# MCU.net
KiCad netlist of a schematic drawn in Altium Designer
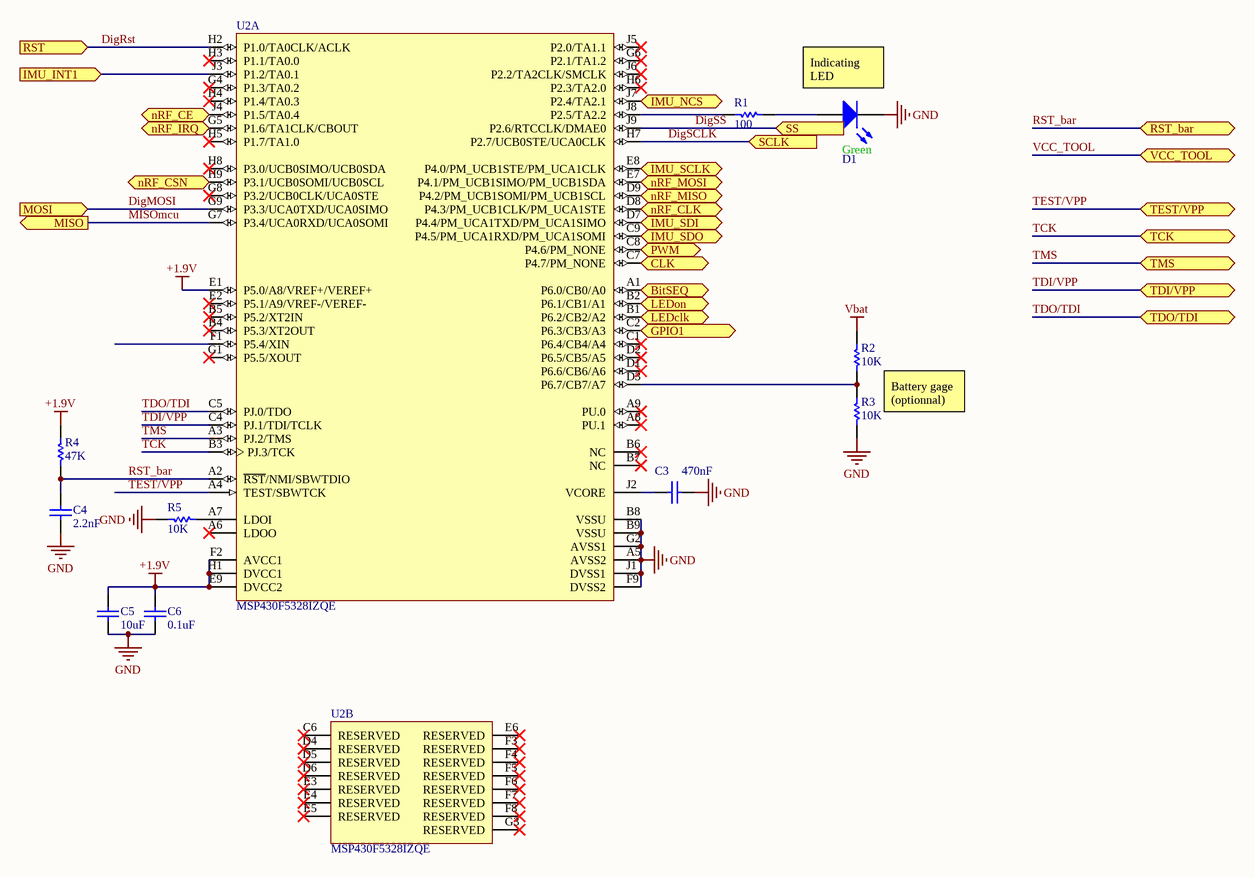
[diagram p0: MCU.SchDoc]

(export (version "E")
  (design (tool "Eeschema 10.0.6"))
  (components
    (comp (ref "C3")
      (value "470nF")
      (footprint "0201_Custom")
      (description "Capacitor (Semiconductor SIM Model)")
      (fields (field (name "PUBLISHER") "Altium Limited"))
      (libsource (lib "Miscellaneous Devices") (part "Cap Semi"))
    )
    (comp (ref "C4")
      (value "2.2nF")
      (footprint "0201_Custom")
      (description "Capacitor (Semiconductor SIM Model)")
      (fields (field (name "PUBLISHER") "Altium Limited"))
      (libsource (lib "Miscellaneous Devices") (part "Cap Semi"))
    )
    (comp (ref "C5")
      (value "10uF")
      (footprint "0402")
      (description "Capacitor (Semiconductor SIM Model)")
      (fields (field (name "PUBLISHER") "Altium Limited"))
      (libsource (lib "Miscellaneous Devices") (part "Cap Semi"))
    )
    (comp (ref "C6")
      (value "0.1uF")
      (footprint "0201_Custom")
      (description "Capacitor (Semiconductor SIM Model)")
      (fields (field (name "PUBLISHER") "Altium Limited"))
      (libsource (lib "Miscellaneous Devices") (part "Cap Semi"))
    )
    (comp (ref "D1")
      (value "~")
      (footprint "0402")
      (description "Typical BLUE SiC LED")
      (fields (field (name "COLOR") "Green") (field (name "PUBLISHER") "Altium Limited"))
      (libsource (lib "Miscellaneous Devices") (part "LED3"))
    )
    (comp (ref "R1")
      (value "100")
      (footprint "0201_Custom")
      (description "Semiconductor Resistor")
      (fields (field (name "PUBLISHER") "Altium Limited"))
      (libsource (lib "Miscellaneous Devices") (part "Res Semi"))
    )
    (comp (ref "R2")
      (value "10K")
      (footprint "0201_Custom")
      (description "Semiconductor Resistor")
      (fields (field (name "PUBLISHER") "Altium Limited"))
      (libsource (lib "Miscellaneous Devices") (part "Res Semi"))
    )
    (comp (ref "R3")
      (value "10K")
      (footprint "0201_Custom")
      (description "Semiconductor Resistor")
      (fields (field (name "PUBLISHER") "Altium Limited"))
      (libsource (lib "Miscellaneous Devices") (part "Res Semi"))
    )
    (comp (ref "R4")
      (value "47K")
      (footprint "0201_Custom")
      (description "Semiconductor Resistor")
      (fields (field (name "PUBLISHER") "Altium Limited"))
      (libsource (lib "Miscellaneous Devices") (part "Res Semi"))
    )
    (comp (ref "R5")
      (value "10K")
      (footprint "0201_Custom")
      (description "Semiconductor Resistor")
      (fields (field (name "PUBLISHER") "Altium Limited"))
      (libsource (lib "Miscellaneous Devices") (part "Res Semi"))
    )
    (comp (ref "U2")
      (value "MSP430F5328IZQE")
      (footprint "TI-ZQE80")
      (fields (field (name "MANUFACTURER") "Texas Instruments"))
      (libsource (lib "TI Microcontroller MSP430 16-bit Ultra-Low Power") (part "MSP430F5328IZQE"))
    )
  )
  (nets
    (net (code "1") (name "+1.9V") (class "Default")
      (node (ref "C5") (pin "2") (pinfunction "2_2") (pintype "passive"))
      (node (ref "C6") (pin "2") (pinfunction "2_2") (pintype "passive"))
      (node (ref "R4") (pin "1") (pinfunction "1_1") (pintype "passive"))
      (node (ref "U2") (pin "E1") (pinfunction "P5.0/A8/VREF+/VEREF+_E1") (pintype "bidirectional"))
      (node (ref "U2") (pin "E9") (pinfunction "DVCC2_E9") (pintype "power_in"))
      (node (ref "U2") (pin "F2") (pinfunction "AVCC1_F2") (pintype "power_in"))
      (node (ref "U2") (pin "H1") (pinfunction "DVCC1_H1") (pintype "power_in"))
    )
    (net (code "2") (name "/BitSEQ") (class "Default")
      (node (ref "U2") (pin "A1") (pinfunction "P6.0/CB0/A0_A1") (pintype "bidirectional"))
    )
    (net (code "3") (name "/CLK") (class "Default")
      (node (ref "U2") (pin "C7") (pinfunction "P4.7/PM_NONE_C7") (pintype "bidirectional"))
    )
    (net (code "4") (name "/DigMOSI") (class "Default")
      (node (ref "U2") (pin "G9") (pinfunction "P3.3/UCA0TXD/UCA0SIMO_G9") (pintype "bidirectional"))
    )
    (net (code "5") (name "/DigRst") (class "Default")
      (node (ref "U2") (pin "H2") (pinfunction "P1.0/TA0CLK/ACLK_H2") (pintype "bidirectional"))
    )
    (net (code "6") (name "/DigSCLK") (class "Default")
      (node (ref "U2") (pin "H7") (pinfunction "P2.7/UCB0STE/UCA0CLK_H7") (pintype "bidirectional"))
    )
    (net (code "7") (name "/DigSS") (class "Default")
      (node (ref "U2") (pin "J9") (pinfunction "P2.6/RTCCLK/DMAE0_J9") (pintype "bidirectional"))
    )
    (net (code "8") (name "/GPIO1") (class "Default")
      (node (ref "U2") (pin "C2") (pinfunction "P6.3/CB3/A3_C2") (pintype "bidirectional"))
    )
    (net (code "9") (name "/IMU_INT1") (class "Default")
      (node (ref "U2") (pin "J3") (pinfunction "P1.2/TA0.1_J3") (pintype "bidirectional"))
    )
    (net (code "10") (name "/IMU_NCS") (class "Default")
      (node (ref "U2") (pin "J7") (pinfunction "P2.4/TA2.1_J7") (pintype "bidirectional"))
    )
    (net (code "11") (name "/IMU_SCLK") (class "Default")
      (node (ref "U2") (pin "E8") (pinfunction "P4.0/PM_UCB1STE/PM_UCA1CLK_E8") (pintype "bidirectional"))
    )
    (net (code "12") (name "/IMU_SDI") (class "Default")
      (node (ref "U2") (pin "D7") (pinfunction "P4.4/PM_UCA1TXD/PM_UCA1SIMO_D7") (pintype "bidirectional"))
    )
    (net (code "13") (name "/IMU_SDO") (class "Default")
      (node (ref "U2") (pin "C9") (pinfunction "P4.5/PM_UCA1RXD/PM_UCA1SOMI_C9") (pintype "bidirectional"))
    )
    (net (code "14") (name "/LEDclk") (class "Default")
      (node (ref "U2") (pin "B1") (pinfunction "P6.2/CB2/A2_B1") (pintype "bidirectional"))
    )
    (net (code "15") (name "/LEDon") (class "Default")
      (node (ref "U2") (pin "B2") (pinfunction "P6.1/CB1/A1_B2") (pintype "bidirectional"))
    )
    (net (code "16") (name "/MISOmcu") (class "Default")
      (node (ref "U2") (pin "G7") (pinfunction "P3.4/UCA0RXD/UCA0SOMI_G7") (pintype "bidirectional"))
    )
    (net (code "17") (name "/PWM") (class "Default")
      (node (ref "U2") (pin "C8") (pinfunction "P4.6/PM_NONE_C8") (pintype "bidirectional"))
    )
    (net (code "18") (name "/RST_bar") (class "Default")
      (node (ref "C4") (pin "1") (pinfunction "1_1") (pintype "passive"))
      (node (ref "R4") (pin "2") (pinfunction "2_2") (pintype "passive"))
      (node (ref "U2") (pin "A2") (pinfunction "~{RST}/NMI/SBWTDIO_A2") (pintype "bidirectional"))
    )
    (net (code "19") (name "/TCK") (class "Default")
      (node (ref "U2") (pin "B3") (pinfunction "PJ.3/TCK_B3") (pintype "bidirectional"))
    )
    (net (code "20") (name "/TDI{slash}VPP") (class "Default")
      (node (ref "U2") (pin "C4") (pinfunction "PJ.1/TDI/TCLK_C4") (pintype "bidirectional"))
    )
    (net (code "21") (name "/TDO{slash}TDI") (class "Default")
      (node (ref "U2") (pin "C5") (pinfunction "PJ.0/TDO_C5") (pintype "bidirectional"))
    )
    (net (code "22") (name "/TEST{slash}VPP") (class "Default")
      (node (ref "U2") (pin "A4") (pinfunction "TEST/SBWTCK_A4") (pintype "input"))
    )
    (net (code "23") (name "/TMS") (class "Default")
      (node (ref "U2") (pin "A3") (pinfunction "PJ.2/TMS_A3") (pintype "bidirectional"))
    )
    (net (code "25") (name "/nRF_CE") (class "Default")
      (node (ref "U2") (pin "J4") (pinfunction "P1.5/TA0.4_J4") (pintype "bidirectional"))
    )
    (net (code "26") (name "/nRF_CLK") (class "Default")
      (node (ref "U2") (pin "D8") (pinfunction "P4.3/PM_UCB1CLK/PM_UCA1STE_D8") (pintype "bidirectional"))
    )
    (net (code "27") (name "/nRF_CSN") (class "Default")
      (node (ref "U2") (pin "H9") (pinfunction "P3.1/UCB0SOMI/UCB0SCL_H9") (pintype "bidirectional"))
    )
    (net (code "28") (name "/nRF_IRQ") (class "Default")
      (node (ref "U2") (pin "G5") (pinfunction "P1.6/TA1CLK/CBOUT_G5") (pintype "bidirectional"))
    )
    (net (code "29") (name "/nRF_MISO") (class "Default")
      (node (ref "U2") (pin "D9") (pinfunction "P4.2/PM_UCB1SOMI/PM_UCB1SCL_D9") (pintype "bidirectional"))
    )
    (net (code "30") (name "/nRF_MOSI") (class "Default")
      (node (ref "U2") (pin "E7") (pinfunction "P4.1/PM_UCB1SIMO/PM_UCB1SDA_E7") (pintype "bidirectional"))
    )
    (net (code "31") (name "GND") (class "Default")
      (node (ref "C3") (pin "1") (pinfunction "1_1") (pintype "passive"))
      (node (ref "C4") (pin "2") (pinfunction "2_2") (pintype "passive"))
      (node (ref "C5") (pin "1") (pinfunction "1_1") (pintype "passive"))
      (node (ref "C6") (pin "1") (pinfunction "1_1") (pintype "passive"))
      (node (ref "D1") (pin "2") (pinfunction "K_2") (pintype "passive"))
      (node (ref "R3") (pin "2") (pinfunction "2_2") (pintype "passive"))
      (node (ref "R5") (pin "2") (pinfunction "2_2") (pintype "passive"))
      (node (ref "U2") (pin "A5") (pinfunction "AVSS2_A5") (pintype "power_in"))
      (node (ref "U2") (pin "B8") (pinfunction "VSSU_B8") (pintype "power_in"))
      (node (ref "U2") (pin "B9") (pinfunction "VSSU_B9") (pintype "power_in"))
      (node (ref "U2") (pin "F9") (pinfunction "DVSS2_F9") (pintype "power_in"))
      (node (ref "U2") (pin "G2") (pinfunction "AVSS1_G2") (pintype "power_in"))
      (node (ref "U2") (pin "J1") (pinfunction "DVSS1_J1") (pintype "power_in"))
    )
    (net (code "32") (name "Net-(D1-A)") (class "Default")
      (node (ref "D1") (pin "1") (pinfunction "A_1") (pintype "passive"))
      (node (ref "R1") (pin "1") (pinfunction "1_1") (pintype "passive"))
    )
    (net (code "33") (name "Net-(U2A-LDOI)") (class "Default")
      (node (ref "R5") (pin "1") (pinfunction "1_1") (pintype "passive"))
      (node (ref "U2") (pin "A7") (pinfunction "LDOI_A7") (pintype "power_in"))
    )
    (net (code "34") (name "Net-(U2A-P2.5{slash}TA2.2)") (class "Default")
      (node (ref "R1") (pin "2") (pinfunction "2_2") (pintype "passive"))
      (node (ref "U2") (pin "J8") (pinfunction "P2.5/TA2.2_J8") (pintype "bidirectional"))
    )
    (net (code "35") (name "Net-(U2A-P6.7{slash}CB7{slash}A7)") (class "Default")
      (node (ref "R2") (pin "2") (pinfunction "2_2") (pintype "passive"))
      (node (ref "R3") (pin "1") (pinfunction "1_1") (pintype "passive"))
      (node (ref "U2") (pin "D3") (pinfunction "P6.7/CB7/A7_D3") (pintype "bidirectional"))
    )
    (net (code "36") (name "Net-(U2A-VCORE)") (class "Default")
      (node (ref "C3") (pin "2") (pinfunction "2_2") (pintype "passive"))
      (node (ref "U2") (pin "J2") (pinfunction "VCORE_J2") (pintype "passive"))
    )
    (net (code "37") (name "Vbat") (class "Default")
      (node (ref "R2") (pin "1") (pinfunction "1_1") (pintype "passive"))
    )
    (net (code "38") (name "unconnected-(U2A-LDOO-PadA6)") (class "Default")
      (node (ref "U2") (pin "A6") (pinfunction "LDOO_A6") (pintype "power_in+no_connect"))
    )
    (net (code "39") (name "unconnected-(U2A-NC-PadB6)") (class "Default")
      (node (ref "U2") (pin "B6") (pinfunction "NC_B6") (pintype "passive+no_connect"))
    )
    (net (code "40") (name "unconnected-(U2A-NC-PadB7)") (class "Default")
      (node (ref "U2") (pin "B7") (pinfunction "NC_B7") (pintype "passive+no_connect"))
    )
    (net (code "41") (name "unconnected-(U2A-P1.1{slash}TA0.0-PadH3)") (class "Default")
      (node (ref "U2") (pin "H3") (pinfunction "P1.1/TA0.0_H3") (pintype "bidirectional+no_connect"))
    )
    (net (code "42") (name "unconnected-(U2A-P1.3{slash}TA0.2-PadG4)") (class "Default")
      (node (ref "U2") (pin "G4") (pinfunction "P1.3/TA0.2_G4") (pintype "bidirectional+no_connect"))
    )
    (net (code "43") (name "unconnected-(U2A-P1.4{slash}TA0.3-PadH4)") (class "Default")
      (node (ref "U2") (pin "H4") (pinfunction "P1.4/TA0.3_H4") (pintype "bidirectional+no_connect"))
    )
    (net (code "44") (name "unconnected-(U2A-P1.7{slash}TA1.0-PadH5)") (class "Default")
      (node (ref "U2") (pin "H5") (pinfunction "P1.7/TA1.0_H5") (pintype "bidirectional+no_connect"))
    )
    (net (code "45") (name "unconnected-(U2A-P2.0{slash}TA1.1-PadJ5)") (class "Default")
      (node (ref "U2") (pin "J5") (pinfunction "P2.0/TA1.1_J5") (pintype "bidirectional+no_connect"))
    )
    (net (code "46") (name "unconnected-(U2A-P2.1{slash}TA1.2-PadG6)") (class "Default")
      (node (ref "U2") (pin "G6") (pinfunction "P2.1/TA1.2_G6") (pintype "bidirectional+no_connect"))
    )
    (net (code "47") (name "unconnected-(U2A-P2.2{slash}TA2CLK{slash}SMCLK-PadJ6)") (class "Default")
      (node (ref "U2") (pin "J6") (pinfunction "P2.2/TA2CLK/SMCLK_J6") (pintype "bidirectional+no_connect"))
    )
    (net (code "48") (name "unconnected-(U2A-P2.3{slash}TA2.0-PadH6)") (class "Default")
      (node (ref "U2") (pin "H6") (pinfunction "P2.3/TA2.0_H6") (pintype "bidirectional+no_connect"))
    )
    (net (code "49") (name "unconnected-(U2A-P3.0{slash}UCB0SIMO{slash}UCB0SDA-PadH8)") (class "Default")
      (node (ref "U2") (pin "H8") (pinfunction "P3.0/UCB0SIMO/UCB0SDA_H8") (pintype "bidirectional+no_connect"))
    )
    (net (code "50") (name "unconnected-(U2A-P3.2{slash}UCB0CLK{slash}UCA0STE-PadG8)") (class "Default")
      (node (ref "U2") (pin "G8") (pinfunction "P3.2/UCB0CLK/UCA0STE_G8") (pintype "bidirectional+no_connect"))
    )
    (net (code "51") (name "unconnected-(U2A-P5.1{slash}A9{slash}VREF-{slash}VEREF--PadE2)") (class "Default")
      (node (ref "U2") (pin "E2") (pinfunction "P5.1/A9/VREF-/VEREF-_E2") (pintype "bidirectional+no_connect"))
    )
    (net (code "52") (name "unconnected-(U2A-P5.2{slash}XT2IN-PadB5)") (class "Default")
      (node (ref "U2") (pin "B5") (pinfunction "P5.2/XT2IN_B5") (pintype "bidirectional+no_connect"))
    )
    (net (code "53") (name "unconnected-(U2A-P5.3{slash}XT2OUT-PadB4)") (class "Default")
      (node (ref "U2") (pin "B4") (pinfunction "P5.3/XT2OUT_B4") (pintype "bidirectional+no_connect"))
    )
    (net (code "54") (name "unconnected-(U2A-P5.4{slash}XIN-PadF1)") (class "Default")
      (node (ref "U2") (pin "F1") (pinfunction "P5.4/XIN_F1") (pintype "bidirectional"))
    )
    (net (code "55") (name "unconnected-(U2A-P5.5{slash}XOUT-PadG1)") (class "Default")
      (node (ref "U2") (pin "G1") (pinfunction "P5.5/XOUT_G1") (pintype "bidirectional+no_connect"))
    )
    (net (code "56") (name "unconnected-(U2A-P6.4{slash}CB4{slash}A4-PadC1)") (class "Default")
      (node (ref "U2") (pin "C1") (pinfunction "P6.4/CB4/A4_C1") (pintype "bidirectional+no_connect"))
    )
    (net (code "57") (name "unconnected-(U2A-P6.5{slash}CB5{slash}A5-PadD2)") (class "Default")
      (node (ref "U2") (pin "D2") (pinfunction "P6.5/CB5/A5_D2") (pintype "bidirectional+no_connect"))
    )
    (net (code "58") (name "unconnected-(U2A-P6.6{slash}CB6{slash}A6-PadD1)") (class "Default")
      (node (ref "U2") (pin "D1") (pinfunction "P6.6/CB6/A6_D1") (pintype "bidirectional+no_connect"))
    )
    (net (code "59") (name "unconnected-(U2A-PU.0-PadA9)") (class "Default")
      (node (ref "U2") (pin "A9") (pinfunction "PU.0_A9") (pintype "bidirectional+no_connect"))
    )
    (net (code "60") (name "unconnected-(U2A-PU.1-PadA8)") (class "Default")
      (node (ref "U2") (pin "A8") (pinfunction "PU.1_A8") (pintype "bidirectional+no_connect"))
    )
    (net (code "61") (name "unconnected-(U2B-RESERVED-PadC6)") (class "Default")
      (node (ref "U2") (pin "C6") (pinfunction "RESERVED_C6") (pintype "passive+no_connect"))
    )
    (net (code "62") (name "unconnected-(U2B-RESERVED-PadD4)") (class "Default")
      (node (ref "U2") (pin "D4") (pinfunction "RESERVED_D4") (pintype "passive+no_connect"))
    )
    (net (code "63") (name "unconnected-(U2B-RESERVED-PadD5)") (class "Default")
      (node (ref "U2") (pin "D5") (pinfunction "RESERVED_D5") (pintype "passive+no_connect"))
    )
    (net (code "64") (name "unconnected-(U2B-RESERVED-PadD6)") (class "Default")
      (node (ref "U2") (pin "D6") (pinfunction "RESERVED_D6") (pintype "passive+no_connect"))
    )
    (net (code "65") (name "unconnected-(U2B-RESERVED-PadE3)") (class "Default")
      (node (ref "U2") (pin "E3") (pinfunction "RESERVED_E3") (pintype "passive+no_connect"))
    )
    (net (code "66") (name "unconnected-(U2B-RESERVED-PadE4)") (class "Default")
      (node (ref "U2") (pin "E4") (pinfunction "RESERVED_E4") (pintype "passive+no_connect"))
    )
    (net (code "67") (name "unconnected-(U2B-RESERVED-PadE5)") (class "Default")
      (node (ref "U2") (pin "E5") (pinfunction "RESERVED_E5") (pintype "passive+no_connect"))
    )
    (net (code "68") (name "unconnected-(U2B-RESERVED-PadE6)") (class "Default")
      (node (ref "U2") (pin "E6") (pinfunction "RESERVED_E6") (pintype "passive+no_connect"))
    )
    (net (code "69") (name "unconnected-(U2B-RESERVED-PadF3)") (class "Default")
      (node (ref "U2") (pin "F3") (pinfunction "RESERVED_F3") (pintype "passive+no_connect"))
    )
    (net (code "70") (name "unconnected-(U2B-RESERVED-PadF4)") (class "Default")
      (node (ref "U2") (pin "F4") (pinfunction "RESERVED_F4") (pintype "passive+no_connect"))
    )
    (net (code "71") (name "unconnected-(U2B-RESERVED-PadF5)") (class "Default")
      (node (ref "U2") (pin "F5") (pinfunction "RESERVED_F5") (pintype "passive+no_connect"))
    )
    (net (code "72") (name "unconnected-(U2B-RESERVED-PadF6)") (class "Default")
      (node (ref "U2") (pin "F6") (pinfunction "RESERVED_F6") (pintype "passive+no_connect"))
    )
    (net (code "73") (name "unconnected-(U2B-RESERVED-PadF7)") (class "Default")
      (node (ref "U2") (pin "F7") (pinfunction "RESERVED_F7") (pintype "passive+no_connect"))
    )
    (net (code "74") (name "unconnected-(U2B-RESERVED-PadF8)") (class "Default")
      (node (ref "U2") (pin "F8") (pinfunction "RESERVED_F8") (pintype "passive+no_connect"))
    )
    (net (code "75") (name "unconnected-(U2B-RESERVED-PadG3)") (class "Default")
      (node (ref "U2") (pin "G3") (pinfunction "RESERVED_G3") (pintype "passive+no_connect"))
    )
  )
)
